# XO_125M.net
KiCad netlist of a schematic drawn in Altium Designer
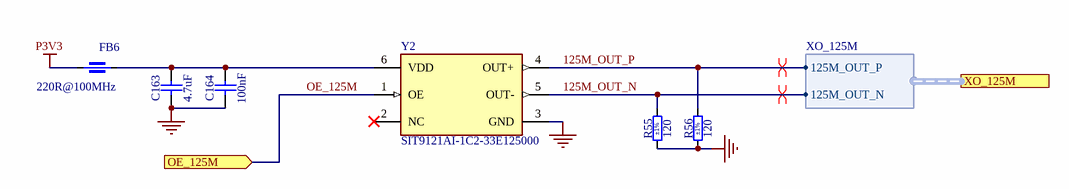
[diagram p0: XO_125M.SchDoc]

(export (version "E")
  (design (tool "Eeschema 10.0.6"))
  (components
    (comp (ref "C163")
      (value "4.7uF")
      (footprint "CAPC1005X55N")
      (description "Non-polarised capacitor")
      (fields
        (field (name "PART NUMBER") "CC0402_4.7UF_6.3V_20%_X5R")
        (field (name "VOLTAGE") "6.3V")
        (field (name "AUTHOR") "CERN DEM JLC")
      )
      (libsource (lib "Capacitors") (part "Capacitor - non polarized"))
    )
    (comp (ref "C164")
      (value "100nF")
      (footprint "CAPC0603X33N")
      (description "Non-polarised capacitor")
      (fields
        (field (name "PART NUMBER") "CC0201_100NF_6.3V_10%_X5R")
        (field (name "VOLTAGE") "6.3V")
        (field (name "AUTHOR") "CERN DEM JLC")
      )
      (libsource (lib "Capacitors") (part "Capacitor - non polarized"))
    )
    (comp (ref "FB6")
      (value "220R@100MHz")
      (footprint "INDC1608X95N")
      (fields
        (field (name "TOLERANCE") "±25%")
        (field (name "PART NUMBER") "IND0603_MURATA_BLM18SG221TN1")
        (field (name "POWER") "2.5A")
        (field (name "AUTHOR") "CERN DEM MR")
      )
      (libsource (lib "Inductors & Transformers") (part "Ferrite Bead"))
    )
    (comp (ref "R55")
      (value "120")
      (footprint "RESC1005X40N")
      (description "Resistor - 1%")
      (fields
        (field (name "TOLERANCE") "±1%")
        (field (name "PART NUMBER") "R0402_120R_1%_0.0625W_100PPM")
        (field (name "POWER") "0.0625W")
        (field (name "AUTHOR") "CERN DEM JLC")
      )
      (libsource (lib "Resistors") (part "Resistor - 1%"))
    )
    (comp (ref "R56")
      (value "120")
      (footprint "RESC1005X40N")
      (description "Resistor - 1%")
      (fields
        (field (name "TOLERANCE") "±1%")
        (field (name "PART NUMBER") "R0402_120R_1%_0.0625W_100PPM")
        (field (name "POWER") "0.0625W")
        (field (name "AUTHOR") "CERN DEM JLC")
      )
      (libsource (lib "Resistors") (part "Resistor - 1%"))
    )
    (comp (ref "Y2")
      (value "SIT9121AI-1C2-33E125000")
      (footprint "FP-SiT9121-C-MFG")
      (description "MEMS OSC XO 125.0000MHZ LVPECL")
      (libsource (lib "Altium Content Vault") (part "46d6734145abd438ebd00756f47ebad"))
    )
  )
  (nets
    (net (code "2") (name "/125M_OUT_N") (class "Default")
      (node (ref "R55") (pin "2") (pinfunction "2_2") (pintype "passive"))
      (node (ref "Y2") (pin "5") (pinfunction "OUT-_5") (pintype "output"))
    )
    (net (code "3") (name "/125M_OUT_P") (class "Default")
      (node (ref "R56") (pin "2") (pinfunction "2_2") (pintype "passive"))
      (node (ref "Y2") (pin "4") (pinfunction "OUT+_4") (pintype "output"))
    )
    (net (code "4") (name "/OE_125M") (class "Default")
      (node (ref "Y2") (pin "1") (pinfunction "OE_1") (pintype "input"))
    )
    (net (code "6") (name "GND") (class "Default")
      (node (ref "C163") (pin "1") (pinfunction "1_1") (pintype "passive"))
      (node (ref "C164") (pin "1") (pinfunction "1_1") (pintype "passive"))
      (node (ref "R55") (pin "1") (pinfunction "1_1") (pintype "passive"))
      (node (ref "R56") (pin "1") (pinfunction "1_1") (pintype "passive"))
      (node (ref "Y2") (pin "3") (pinfunction "GND_3") (pintype "power_in"))
    )
    (net (code "7") (name "Net-(Y2-VDD)") (class "Default")
      (node (ref "C163") (pin "2") (pinfunction "2_2") (pintype "passive"))
      (node (ref "C164") (pin "2") (pinfunction "2_2") (pintype "passive"))
      (node (ref "FB6") (pin "2") (pinfunction "2_2") (pintype "passive"))
      (node (ref "Y2") (pin "6") (pinfunction "VDD_6") (pintype "power_in"))
    )
    (net (code "8") (name "P3V3") (class "Default")
      (node (ref "FB6") (pin "1") (pinfunction "1_1") (pintype "passive"))
    )
    (net (code "9") (name "unconnected-(Y2-NC-Pad2)") (class "Default")
      (node (ref "Y2") (pin "2") (pinfunction "NC_2") (pintype "passive+no_connect"))
    )
  )
)
